# usb415.net
KiCad netlist of a schematic drawn in EAGLE
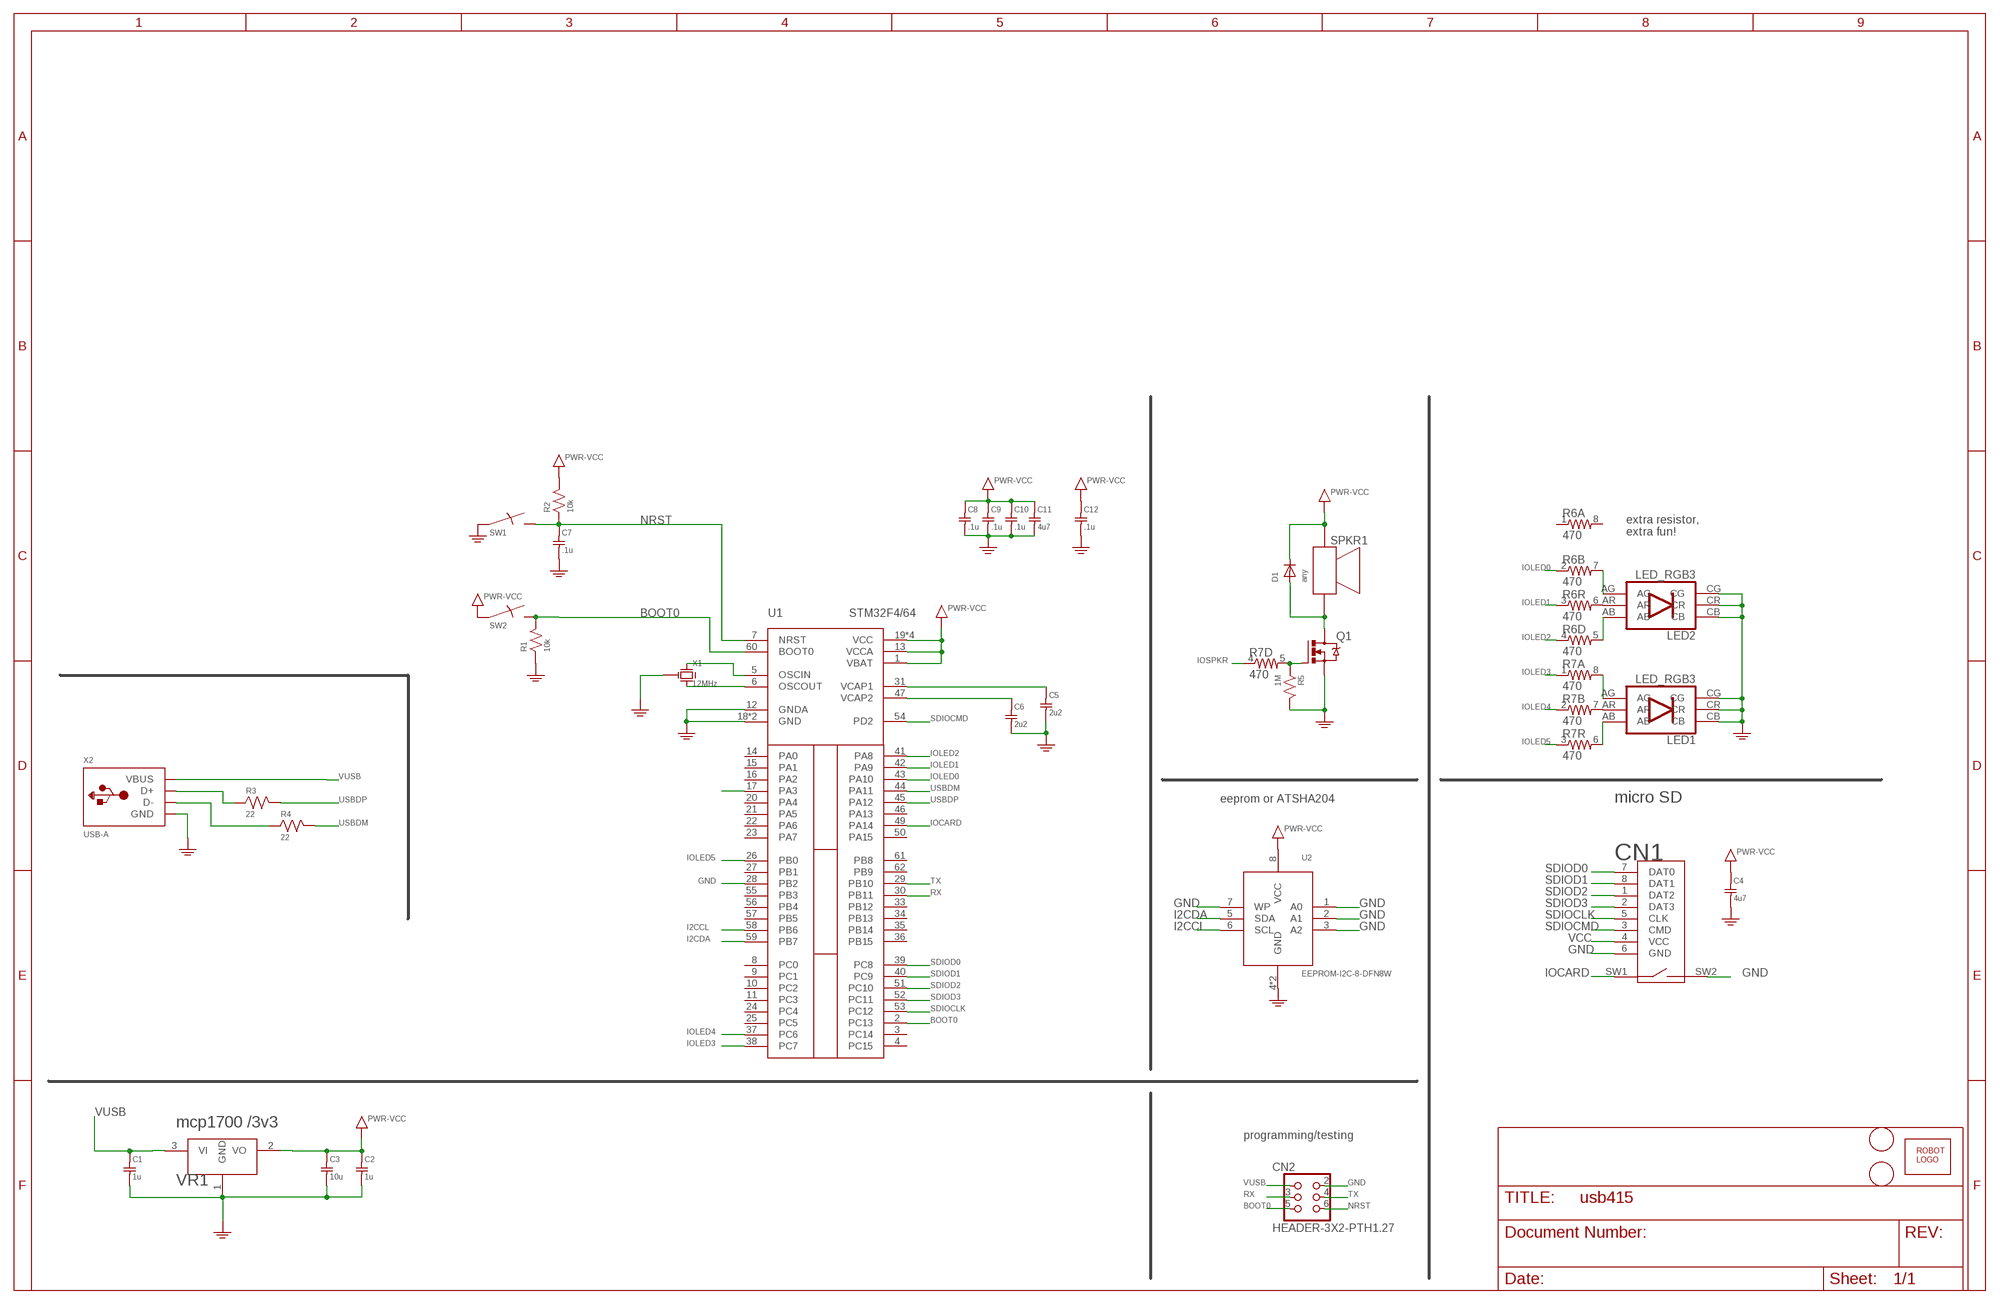
[diagram p0: schematic, sheet 1]

(export (version "E")
  (design (tool "Eeschema 10.0.6"))
  (components
    (comp (ref "C1")
      (value "1u")
      (footprint "eagle-import:SMD0603")
      (libsource (lib "eagle-import") (part "C0603"))
    )
    (comp (ref "C2")
      (value "1u")
      (footprint "eagle-import:SMD0603")
      (libsource (lib "eagle-import") (part "C0603"))
    )
    (comp (ref "C3")
      (value "10u")
      (footprint "eagle-import:SMD0603")
      (libsource (lib "eagle-import") (part "C0603"))
    )
    (comp (ref "C4")
      (value "4u7")
      (footprint "eagle-import:SMD0603")
      (libsource (lib "eagle-import") (part "C0603"))
    )
    (comp (ref "C5")
      (value "2u2")
      (footprint "eagle-import:SMD0603")
      (libsource (lib "eagle-import") (part "C0603"))
    )
    (comp (ref "C6")
      (value "2u2")
      (footprint "eagle-import:SMD0603")
      (libsource (lib "eagle-import") (part "C0603"))
    )
    (comp (ref "C7")
      (value ".1u")
      (footprint "eagle-import:SMD0603")
      (libsource (lib "eagle-import") (part "C0603"))
    )
    (comp (ref "C8")
      (value ".1u")
      (footprint "eagle-import:SMD0603")
      (libsource (lib "eagle-import") (part "C0603"))
    )
    (comp (ref "C9")
      (value ".1u")
      (footprint "eagle-import:SMD0603")
      (libsource (lib "eagle-import") (part "C0603"))
    )
    (comp (ref "C10")
      (value ".1u")
      (footprint "eagle-import:SMD0603")
      (libsource (lib "eagle-import") (part "C0603"))
    )
    (comp (ref "C11")
      (value "4u7")
      (footprint "eagle-import:SMD0603")
      (libsource (lib "eagle-import") (part "C0603"))
    )
    (comp (ref "C12")
      (value ".1u")
      (footprint "eagle-import:SMD0603")
      (libsource (lib "eagle-import") (part "C0603"))
    )
    (comp (ref "CN1")
      (value "MICROSDPLAIN")
      (footprint "eagle-import:MICROSD_MOLEX_FRONT_PLAIN")
      (libsource (lib "eagle-import") (part "MICROSDPLAIN"))
    )
    (comp (ref "CN2")
      (value "HEADER-3X2-PTH1.27")
      (footprint "eagle-import:HEADER-3X2-PTH1.27")
      (libsource (lib "eagle-import") (part "HEADER-3X2-PTH1.27"))
    )
    (comp (ref "D1")
      (value "any")
      (footprint "eagle-import:SOD-323")
      (libsource (lib "eagle-import") (part "DIODESOD-323"))
    )
    (comp (ref "LED1")
      (value "LED_RGB3")
      (footprint "eagle-import:SMDLEDRGB")
      (libsource (lib "eagle-import") (part "LED_RGB3"))
    )
    (comp (ref "LED2")
      (value "LED_RGB3")
      (footprint "eagle-import:SMDLEDRGB")
      (libsource (lib "eagle-import") (part "LED_RGB3"))
    )
    (comp (ref "Q1")
      (value "IRLML6344TRPBF")
      (footprint "eagle-import:SOT-23")
      (libsource (lib "eagle-import") (part "MOSFETSOT-23"))
    )
    (comp (ref "R1")
      (value "10k")
      (footprint "eagle-import:SMD0603")
      (libsource (lib "eagle-import") (part "R0603"))
    )
    (comp (ref "R2")
      (value "10k")
      (footprint "eagle-import:SMD0603")
      (libsource (lib "eagle-import") (part "R0603"))
    )
    (comp (ref "R3")
      (value "22")
      (footprint "eagle-import:SMD0603")
      (libsource (lib "eagle-import") (part "R0603"))
    )
    (comp (ref "R4")
      (value "22")
      (footprint "eagle-import:SMD0603")
      (libsource (lib "eagle-import") (part "R0603"))
    )
    (comp (ref "R5")
      (value "1M")
      (footprint "eagle-import:SMD0603")
      (libsource (lib "eagle-import") (part "R0603"))
    )
    (comp (ref "R6")
      (value "470")
      (footprint "eagle-import:SMD-0603-ARV")
      (libsource (lib "eagle-import") (part "R-ARRAY40603-ARV"))
    )
    (comp (ref "R7")
      (value "470")
      (footprint "eagle-import:SMD-0603-ARV")
      (libsource (lib "eagle-import") (part "R-ARRAY40603-ARV"))
    )
    (comp (ref "SPKR1")
      (value "SPKR-PUI-0440")
      (footprint "eagle-import:PUI-0440")
      (libsource (lib "eagle-import") (part "SPKR-PUI-0440"))
    )
    (comp (ref "SW1")
      (value "SWITCHKMR211")
      (footprint "eagle-import:KMR211")
      (libsource (lib "eagle-import") (part "SWITCHKMR211"))
    )
    (comp (ref "SW2")
      (value "SWITCHKMR211")
      (footprint "eagle-import:KMR211")
      (libsource (lib "eagle-import") (part "SWITCHKMR211"))
    )
    (comp (ref "U$1")
      (value "ROBOTMAN-LOGO")
      (footprint "eagle-import:ROBOTMAN-LOGO")
      (libsource (lib "eagle-import") (part "ROBOTMAN-LOGO"))
    )
    (comp (ref "U$2")
      (value "FIDUCIAL")
      (footprint "eagle-import:FIDUCIAL_1MM")
      (libsource (lib "eagle-import") (part "FIDUCIAL"))
    )
    (comp (ref "U$3")
      (value "FIDUCIAL")
      (footprint "eagle-import:FIDUCIAL_1MM")
      (libsource (lib "eagle-import") (part "FIDUCIAL"))
    )
    (comp (ref "U1")
      (value "STM32F4/64")
      (footprint "eagle-import:TQFP64")
      (libsource (lib "eagle-import") (part "STM32F4/64"))
    )
    (comp (ref "U2")
      (value "EEPROM-I2C-8-DFN8W")
      (footprint "eagle-import:TDFN8EPW")
      (libsource (lib "eagle-import") (part "EEPROM-I2C-8-DFN8W"))
    )
    (comp (ref "VR1")
      (value "mcp1700 /3v3")
      (footprint "eagle-import:SOT-23-3")
      (libsource (lib "eagle-import") (part "REGULATOR-SOT23-3"))
    )
    (comp (ref "X1")
      (value "12MHz")
      (footprint "eagle-import:RESONATOR-CSTCE")
      (libsource (lib "eagle-import") (part "RESONATORCTCE"))
    )
    (comp (ref "X2")
      (value "USB-A")
      (footprint "eagle-import:MOLEX_480371000")
      (libsource (lib "eagle-import") (part "USB-A"))
    )
  )
  (nets
    (net (code "1") (name "/BOOT0") (class "Default")
      (node (ref "CN2") (pin "5") (pinfunction "P$5_5") (pintype "passive"))
      (node (ref "R1") (pin "2") (pinfunction "P$2_2") (pintype "passive"))
      (node (ref "SW2") (pin "2") (pinfunction "P$2_2") (pintype "passive"))
      (node (ref "SW2") (pin "4") (pinfunction "P$2_4") (pintype "passive"))
      (node (ref "U1") (pin "2") (pinfunction "PC13_2") (pintype "bidirectional"))
      (node (ref "U1") (pin "60") (pinfunction "BOOT0_60") (pintype "bidirectional"))
    )
    (net (code "2") (name "/I2CCL") (class "Default")
      (node (ref "U1") (pin "58") (pinfunction "PB6_58") (pintype "bidirectional"))
      (node (ref "U2") (pin "6") (pinfunction "SCL_6") (pintype "bidirectional"))
    )
    (net (code "3") (name "/I2CDA") (class "Default")
      (node (ref "U1") (pin "59") (pinfunction "PB7_59") (pintype "bidirectional"))
      (node (ref "U2") (pin "5") (pinfunction "SDA_5") (pintype "bidirectional"))
    )
    (net (code "4") (name "/IOCARD") (class "Default")
      (node (ref "CN1") (pin "SW1") (pinfunction "SW1_SW1") (pintype "bidirectional"))
      (node (ref "U1") (pin "49") (pinfunction "PA14_49") (pintype "bidirectional"))
    )
    (net (code "5") (name "/IOLED0") (class "Default")
      (node (ref "R6") (pin "2") (pinfunction "1_2") (pintype "passive"))
      (node (ref "U1") (pin "43") (pinfunction "PA10_43") (pintype "bidirectional"))
    )
    (net (code "6") (name "/IOLED1") (class "Default")
      (node (ref "R6") (pin "3") (pinfunction "1_3") (pintype "passive"))
      (node (ref "U1") (pin "42") (pinfunction "PA9_42") (pintype "bidirectional"))
    )
    (net (code "7") (name "/IOLED2") (class "Default")
      (node (ref "R6") (pin "4") (pinfunction "1_4") (pintype "passive"))
      (node (ref "U1") (pin "41") (pinfunction "PA8_41") (pintype "bidirectional"))
    )
    (net (code "8") (name "/IOLED3") (class "Default")
      (node (ref "R7") (pin "1") (pinfunction "1_1") (pintype "passive"))
      (node (ref "U1") (pin "38") (pinfunction "PC7_38") (pintype "bidirectional"))
    )
    (net (code "9") (name "/IOLED4") (class "Default")
      (node (ref "R7") (pin "2") (pinfunction "1_2") (pintype "passive"))
      (node (ref "U1") (pin "37") (pinfunction "PC6_37") (pintype "bidirectional"))
    )
    (net (code "10") (name "/IOLED5") (class "Default")
      (node (ref "R7") (pin "3") (pinfunction "1_3") (pintype "passive"))
      (node (ref "U1") (pin "26") (pinfunction "PB0_26") (pintype "bidirectional"))
    )
    (net (code "11") (name "/IOSPKR") (class "Default")
      (node (ref "R7") (pin "4") (pinfunction "1_4") (pintype "passive"))
      (node (ref "U1") (pin "17") (pinfunction "PA3_17") (pintype "bidirectional"))
    )
    (net (code "12") (name "/NRST") (class "Default")
      (node (ref "C7") (pin "1") (pinfunction "P$1_1") (pintype "passive"))
      (node (ref "CN2") (pin "6") (pinfunction "P$6_6") (pintype "passive"))
      (node (ref "R2") (pin "1") (pinfunction "P$1_1") (pintype "passive"))
      (node (ref "SW1") (pin "2") (pinfunction "P$2_2") (pintype "passive"))
      (node (ref "SW1") (pin "4") (pinfunction "P$2_4") (pintype "passive"))
      (node (ref "U1") (pin "7") (pinfunction "NRST_7") (pintype "bidirectional"))
    )
    (net (code "13") (name "/RX") (class "Default")
      (node (ref "CN2") (pin "3") (pinfunction "P$3_3") (pintype "passive"))
      (node (ref "U1") (pin "30") (pinfunction "PB11_30") (pintype "bidirectional"))
    )
    (net (code "14") (name "/SDIOCLK") (class "Default")
      (node (ref "CN1") (pin "5") (pinfunction "CLK_5") (pintype "bidirectional"))
      (node (ref "U1") (pin "53") (pinfunction "PC12_53") (pintype "bidirectional"))
    )
    (net (code "15") (name "/SDIOCMD") (class "Default")
      (node (ref "CN1") (pin "3") (pinfunction "CMD_3") (pintype "bidirectional"))
      (node (ref "U1") (pin "54") (pinfunction "PD2_54") (pintype "bidirectional"))
    )
    (net (code "16") (name "/SDIOD0") (class "Default")
      (node (ref "CN1") (pin "7") (pinfunction "DAT0_7") (pintype "bidirectional"))
      (node (ref "U1") (pin "39") (pinfunction "PC8_39") (pintype "bidirectional"))
    )
    (net (code "17") (name "/SDIOD1") (class "Default")
      (node (ref "CN1") (pin "8") (pinfunction "DAT1_8") (pintype "bidirectional"))
      (node (ref "U1") (pin "40") (pinfunction "PC9_40") (pintype "bidirectional"))
    )
    (net (code "18") (name "/SDIOD2") (class "Default")
      (node (ref "CN1") (pin "1") (pinfunction "DAT2_1") (pintype "bidirectional"))
      (node (ref "U1") (pin "51") (pinfunction "PC10_51") (pintype "bidirectional"))
    )
    (net (code "19") (name "/SDIOD3") (class "Default")
      (node (ref "CN1") (pin "2") (pinfunction "DAT3_2") (pintype "bidirectional"))
      (node (ref "U1") (pin "52") (pinfunction "PC11_52") (pintype "bidirectional"))
    )
    (net (code "20") (name "/TX") (class "Default")
      (node (ref "CN2") (pin "4") (pinfunction "P$4_4") (pintype "passive"))
      (node (ref "U1") (pin "29") (pinfunction "PB10_29") (pintype "bidirectional"))
    )
    (net (code "21") (name "/USBDM") (class "Default")
      (node (ref "R4") (pin "2") (pinfunction "P$2_2") (pintype "passive"))
      (node (ref "U1") (pin "44") (pinfunction "PA11_44") (pintype "bidirectional"))
    )
    (net (code "22") (name "/USBDP") (class "Default")
      (node (ref "R3") (pin "2") (pinfunction "P$2_2") (pintype "passive"))
      (node (ref "U1") (pin "45") (pinfunction "PA12_45") (pintype "bidirectional"))
    )
    (net (code "23") (name "/VUSB") (class "Default")
      (node (ref "C1") (pin "1") (pinfunction "P$1_1") (pintype "passive"))
      (node (ref "CN2") (pin "1") (pinfunction "P$1_1") (pintype "passive"))
      (node (ref "VR1") (pin "3") (pinfunction "VI_3") (pintype "bidirectional"))
      (node (ref "X2") (pin "1") (pinfunction "VBUS_1") (pintype "power_in"))
    )
    (net (code "24") (name "Net-(C5-P$1)") (class "Default")
      (node (ref "C5") (pin "1") (pinfunction "P$1_1") (pintype "passive"))
      (node (ref "U1") (pin "31") (pinfunction "VCAP1_31") (pintype "bidirectional"))
    )
    (net (code "25") (name "Net-(C6-P$1)") (class "Default")
      (node (ref "C6") (pin "1") (pinfunction "P$1_1") (pintype "passive"))
      (node (ref "U1") (pin "47") (pinfunction "VCAP2_47") (pintype "bidirectional"))
    )
    (net (code "26") (name "Net-(Q1-D)") (class "Default")
      (node (ref "D1") (pin "A") (pinfunction "A_A") (pintype "passive"))
      (node (ref "Q1") (pin "3") (pinfunction "D_3") (pintype "passive"))
      (node (ref "SPKR1") (pin "P$2") (pinfunction "P2_P$2") (pintype "input"))
    )
    (net (code "27") (name "Net-(Q1-G)") (class "Default")
      (node (ref "Q1") (pin "1") (pinfunction "G_1") (pintype "passive"))
      (node (ref "R5") (pin "1") (pinfunction "P$1_1") (pintype "passive"))
      (node (ref "R7") (pin "5") (pinfunction "2_5") (pintype "passive"))
    )
    (net (code "28") (name "Net-(R3-P$1)") (class "Default")
      (node (ref "R3") (pin "1") (pinfunction "P$1_1") (pintype "passive"))
      (node (ref "X2") (pin "3") (pinfunction "D+_3") (pintype "bidirectional"))
    )
    (net (code "29") (name "Net-(R4-P$1)") (class "Default")
      (node (ref "R4") (pin "1") (pinfunction "P$1_1") (pintype "passive"))
      (node (ref "X2") (pin "2") (pinfunction "D-_2") (pintype "bidirectional"))
    )
    (net (code "30") (name "Net-(R6B-2)") (class "Default")
      (node (ref "LED2") (pin "AG") (pinfunction "AG_AG") (pintype "bidirectional"))
      (node (ref "R6") (pin "7") (pinfunction "2_7") (pintype "passive"))
    )
    (net (code "31") (name "Net-(R6C-2)") (class "Default")
      (node (ref "LED2") (pin "AB") (pinfunction "AB_AB") (pintype "bidirectional"))
      (node (ref "R6") (pin "5") (pinfunction "2_5") (pintype "passive"))
    )
    (net (code "32") (name "Net-(R6D-2)") (class "Default")
      (node (ref "LED2") (pin "AR") (pinfunction "AR_AR") (pintype "bidirectional"))
      (node (ref "R6") (pin "6") (pinfunction "2_6") (pintype "passive"))
    )
    (net (code "33") (name "Net-(R7A-2)") (class "Default")
      (node (ref "LED1") (pin "AG") (pinfunction "AG_AG") (pintype "bidirectional"))
      (node (ref "R7") (pin "8") (pinfunction "2_8") (pintype "passive"))
    )
    (net (code "34") (name "Net-(R7B-2)") (class "Default")
      (node (ref "LED1") (pin "AR") (pinfunction "AR_AR") (pintype "bidirectional"))
      (node (ref "R7") (pin "7") (pinfunction "2_7") (pintype "passive"))
    )
    (net (code "35") (name "Net-(R7D-2)") (class "Default")
      (node (ref "LED1") (pin "AB") (pinfunction "AB_AB") (pintype "bidirectional"))
      (node (ref "R7") (pin "6") (pinfunction "2_6") (pintype "passive"))
    )
    (net (code "36") (name "Net-(U1-OSCIN)") (class "Default")
      (node (ref "U1") (pin "5") (pinfunction "OSCIN_5") (pintype "bidirectional"))
      (node (ref "X1") (pin "1") (pinfunction "X1_1") (pintype "passive"))
    )
    (net (code "37") (name "Net-(U1-OSCOUT)") (class "Default")
      (node (ref "U1") (pin "6") (pinfunction "OSCOUT_6") (pintype "bidirectional"))
      (node (ref "X1") (pin "3") (pinfunction "X2_3") (pintype "passive"))
    )
    (net (code "38") (name "PWR-GND") (class "Default")
      (node (ref "C1") (pin "2") (pinfunction "P$2_2") (pintype "passive"))
      (node (ref "C10") (pin "2") (pinfunction "P$2_2") (pintype "passive"))
      (node (ref "C11") (pin "2") (pinfunction "P$2_2") (pintype "passive"))
      (node (ref "C12") (pin "2") (pinfunction "P$2_2") (pintype "passive"))
      (node (ref "C2") (pin "2") (pinfunction "P$2_2") (pintype "passive"))
      (node (ref "C3") (pin "2") (pinfunction "P$2_2") (pintype "passive"))
      (node (ref "C4") (pin "2") (pinfunction "P$2_2") (pintype "passive"))
      (node (ref "C5") (pin "2") (pinfunction "P$2_2") (pintype "passive"))
      (node (ref "C6") (pin "2") (pinfunction "P$2_2") (pintype "passive"))
      (node (ref "C7") (pin "2") (pinfunction "P$2_2") (pintype "passive"))
      (node (ref "C8") (pin "2") (pinfunction "P$2_2") (pintype "passive"))
      (node (ref "C9") (pin "2") (pinfunction "P$2_2") (pintype "passive"))
      (node (ref "CN1") (pin "6") (pinfunction "GND_6") (pintype "bidirectional"))
      (node (ref "CN1") (pin "SW2") (pinfunction "SW2_SW2") (pintype "bidirectional"))
      (node (ref "CN2") (pin "2") (pinfunction "P$2_2") (pintype "passive"))
      (node (ref "LED1") (pin "CB") (pinfunction "CB_CB") (pintype "bidirectional"))
      (node (ref "LED1") (pin "CG") (pinfunction "CG_CG") (pintype "bidirectional"))
      (node (ref "LED1") (pin "CR") (pinfunction "CR_CR") (pintype "bidirectional"))
      (node (ref "LED2") (pin "CB") (pinfunction "CB_CB") (pintype "bidirectional"))
      (node (ref "LED2") (pin "CG") (pinfunction "CG_CG") (pintype "bidirectional"))
      (node (ref "LED2") (pin "CR") (pinfunction "CR_CR") (pintype "bidirectional"))
      (node (ref "Q1") (pin "2") (pinfunction "S_2") (pintype "passive"))
      (node (ref "R1") (pin "1") (pinfunction "P$1_1") (pintype "passive"))
      (node (ref "R5") (pin "2") (pinfunction "P$2_2") (pintype "passive"))
      (node (ref "SW1") (pin "1") (pinfunction "P$1_1") (pintype "passive"))
      (node (ref "SW1") (pin "3") (pinfunction "P$1_3") (pintype "passive"))
      (node (ref "U1") (pin "12") (pinfunction "GNDA_12") (pintype "bidirectional"))
      (node (ref "U1") (pin "18") (pinfunction "GND_18") (pintype "bidirectional"))
      (node (ref "U1") (pin "28") (pinfunction "PB2_28") (pintype "bidirectional"))
      (node (ref "U1") (pin "63") (pinfunction "GND_63") (pintype "bidirectional"))
      (node (ref "U2") (pin "1") (pinfunction "A0_1") (pintype "bidirectional"))
      (node (ref "U2") (pin "2") (pinfunction "A1_2") (pintype "bidirectional"))
      (node (ref "U2") (pin "3") (pinfunction "A2_3") (pintype "bidirectional"))
      (node (ref "U2") (pin "4") (pinfunction "GND_4") (pintype "bidirectional"))
      (node (ref "U2") (pin "7") (pinfunction "WP_7") (pintype "bidirectional"))
      (node (ref "U2") (pin "PAD") (pinfunction "GND_PAD") (pintype "bidirectional"))
      (node (ref "VR1") (pin "1") (pinfunction "GND_1") (pintype "bidirectional"))
      (node (ref "X1") (pin "2") (pinfunction "G_2") (pintype "input"))
      (node (ref "X2") (pin "4") (pinfunction "GND_4") (pintype "power_in"))
    )
    (net (code "39") (name "PWR-VCC") (class "Default")
      (node (ref "C10") (pin "1") (pinfunction "P$1_1") (pintype "passive"))
      (node (ref "C11") (pin "1") (pinfunction "P$1_1") (pintype "passive"))
      (node (ref "C12") (pin "1") (pinfunction "P$1_1") (pintype "passive"))
      (node (ref "C2") (pin "1") (pinfunction "P$1_1") (pintype "passive"))
      (node (ref "C3") (pin "1") (pinfunction "P$1_1") (pintype "passive"))
      (node (ref "C4") (pin "1") (pinfunction "P$1_1") (pintype "passive"))
      (node (ref "C8") (pin "1") (pinfunction "P$1_1") (pintype "passive"))
      (node (ref "C9") (pin "1") (pinfunction "P$1_1") (pintype "passive"))
      (node (ref "CN1") (pin "4") (pinfunction "VCC_4") (pintype "bidirectional"))
      (node (ref "D1") (pin "C") (pinfunction "C_C") (pintype "passive"))
      (node (ref "R2") (pin "2") (pinfunction "P$2_2") (pintype "passive"))
      (node (ref "SPKR1") (pin "P$1") (pinfunction "P1_P$1") (pintype "input"))
      (node (ref "SW2") (pin "1") (pinfunction "P$1_1") (pintype "passive"))
      (node (ref "SW2") (pin "3") (pinfunction "P$1_3") (pintype "passive"))
      (node (ref "U1") (pin "1") (pinfunction "VBAT_1") (pintype "bidirectional"))
      (node (ref "U1") (pin "13") (pinfunction "VCCA_13") (pintype "bidirectional"))
      (node (ref "U1") (pin "19") (pinfunction "VCC_19") (pintype "bidirectional"))
      (node (ref "U1") (pin "32") (pinfunction "VCC_32") (pintype "bidirectional"))
      (node (ref "U1") (pin "48") (pinfunction "VCC_48") (pintype "bidirectional"))
      (node (ref "U1") (pin "64") (pinfunction "VCC_64") (pintype "bidirectional"))
      (node (ref "U2") (pin "8") (pinfunction "VCC_8") (pintype "bidirectional"))
      (node (ref "VR1") (pin "2") (pinfunction "VO_2") (pintype "bidirectional"))
    )
    (net (code "40") (name "unconnected-(R6-Pad1)") (class "Default")
      (node (ref "R6") (pin "1") (pinfunction "1_1") (pintype "passive"))
    )
    (net (code "41") (name "unconnected-(R6A-2-Pad8)") (class "Default")
      (node (ref "R6") (pin "8") (pinfunction "2_8") (pintype "passive"))
    )
    (net (code "42") (name "unconnected-(U1-PA0-Pad14)") (class "Default")
      (node (ref "U1") (pin "14") (pinfunction "PA0_14") (pintype "bidirectional"))
    )
    (net (code "43") (name "unconnected-(U1-PA1-Pad15)") (class "Default")
      (node (ref "U1") (pin "15") (pinfunction "PA1_15") (pintype "bidirectional"))
    )
    (net (code "44") (name "unconnected-(U1-PA2-Pad16)") (class "Default")
      (node (ref "U1") (pin "16") (pinfunction "PA2_16") (pintype "bidirectional"))
    )
    (net (code "45") (name "unconnected-(U1-PA4-Pad20)") (class "Default")
      (node (ref "U1") (pin "20") (pinfunction "PA4_20") (pintype "bidirectional"))
    )
    (net (code "46") (name "unconnected-(U1-PA5-Pad21)") (class "Default")
      (node (ref "U1") (pin "21") (pinfunction "PA5_21") (pintype "bidirectional"))
    )
    (net (code "47") (name "unconnected-(U1-PA6-Pad22)") (class "Default")
      (node (ref "U1") (pin "22") (pinfunction "PA6_22") (pintype "bidirectional"))
    )
    (net (code "48") (name "unconnected-(U1-PA7-Pad23)") (class "Default")
      (node (ref "U1") (pin "23") (pinfunction "PA7_23") (pintype "bidirectional"))
    )
    (net (code "49") (name "unconnected-(U1-PA13-Pad46)") (class "Default")
      (node (ref "U1") (pin "46") (pinfunction "PA13_46") (pintype "bidirectional"))
    )
    (net (code "50") (name "unconnected-(U1-PA15-Pad50)") (class "Default")
      (node (ref "U1") (pin "50") (pinfunction "PA15_50") (pintype "bidirectional"))
    )
    (net (code "51") (name "unconnected-(U1-PB1-Pad27)") (class "Default")
      (node (ref "U1") (pin "27") (pinfunction "PB1_27") (pintype "bidirectional"))
    )
    (net (code "52") (name "unconnected-(U1-PB3-Pad55)") (class "Default")
      (node (ref "U1") (pin "55") (pinfunction "PB3_55") (pintype "bidirectional"))
    )
    (net (code "53") (name "unconnected-(U1-PB4-Pad56)") (class "Default")
      (node (ref "U1") (pin "56") (pinfunction "PB4_56") (pintype "bidirectional"))
    )
    (net (code "54") (name "unconnected-(U1-PB5-Pad57)") (class "Default")
      (node (ref "U1") (pin "57") (pinfunction "PB5_57") (pintype "bidirectional"))
    )
    (net (code "55") (name "unconnected-(U1-PB8-Pad61)") (class "Default")
      (node (ref "U1") (pin "61") (pinfunction "PB8_61") (pintype "bidirectional"))
    )
    (net (code "56") (name "unconnected-(U1-PB9-Pad62)") (class "Default")
      (node (ref "U1") (pin "62") (pinfunction "PB9_62") (pintype "bidirectional"))
    )
    (net (code "57") (name "unconnected-(U1-PB12-Pad33)") (class "Default")
      (node (ref "U1") (pin "33") (pinfunction "PB12_33") (pintype "bidirectional"))
    )
    (net (code "58") (name "unconnected-(U1-PB13-Pad34)") (class "Default")
      (node (ref "U1") (pin "34") (pinfunction "PB13_34") (pintype "bidirectional"))
    )
    (net (code "59") (name "unconnected-(U1-PB14-Pad35)") (class "Default")
      (node (ref "U1") (pin "35") (pinfunction "PB14_35") (pintype "bidirectional"))
    )
    (net (code "60") (name "unconnected-(U1-PB15-Pad36)") (class "Default")
      (node (ref "U1") (pin "36") (pinfunction "PB15_36") (pintype "bidirectional"))
    )
    (net (code "61") (name "unconnected-(U1-PC0-Pad8)") (class "Default")
      (node (ref "U1") (pin "8") (pinfunction "PC0_8") (pintype "bidirectional"))
    )
    (net (code "62") (name "unconnected-(U1-PC1-Pad9)") (class "Default")
      (node (ref "U1") (pin "9") (pinfunction "PC1_9") (pintype "bidirectional"))
    )
    (net (code "63") (name "unconnected-(U1-PC2-Pad10)") (class "Default")
      (node (ref "U1") (pin "10") (pinfunction "PC2_10") (pintype "bidirectional"))
    )
    (net (code "64") (name "unconnected-(U1-PC3-Pad11)") (class "Default")
      (node (ref "U1") (pin "11") (pinfunction "PC3_11") (pintype "bidirectional"))
    )
    (net (code "65") (name "unconnected-(U1-PC4-Pad24)") (class "Default")
      (node (ref "U1") (pin "24") (pinfunction "PC4_24") (pintype "bidirectional"))
    )
    (net (code "66") (name "unconnected-(U1-PC5-Pad25)") (class "Default")
      (node (ref "U1") (pin "25") (pinfunction "PC5_25") (pintype "bidirectional"))
    )
    (net (code "67") (name "unconnected-(U1-PC14-Pad3)") (class "Default")
      (node (ref "U1") (pin "3") (pinfunction "PC14_3") (pintype "bidirectional"))
    )
    (net (code "68") (name "unconnected-(U1-PC15-Pad4)") (class "Default")
      (node (ref "U1") (pin "4") (pinfunction "PC15_4") (pintype "bidirectional"))
    )
  )
)
